# pwr_block.net
KiCad netlist of a schematic drawn in EAGLE
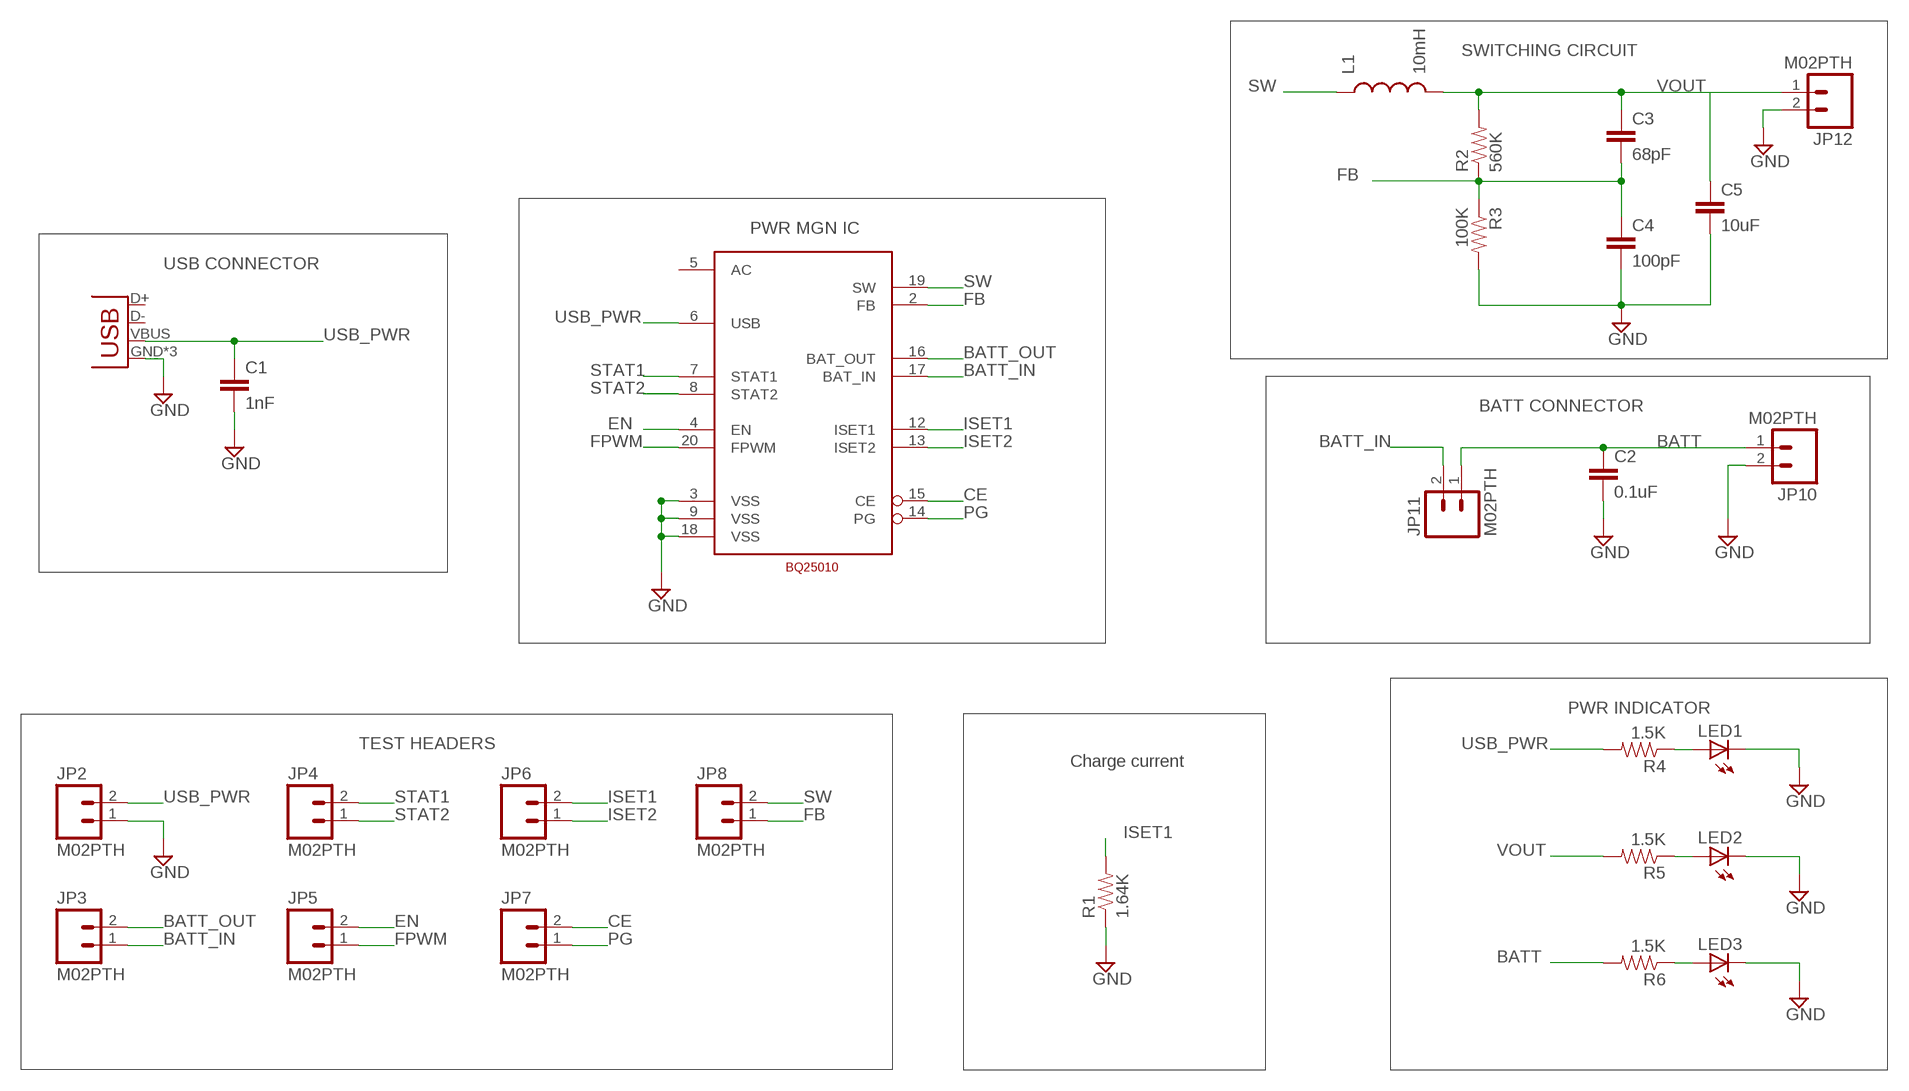
[diagram p0: schematic, sheet 1]

(export (version "E")
  (design (tool "Eeschema 10.0.6"))
  (components
    (comp (ref "C1")
      (value "1nF")
      (footprint "eagle-import:0603-CAP")
      (libsource (lib "eagle-import") (part "1NF/1000PF-50V-10%(0603)"))
    )
    (comp (ref "C2")
      (value "0.1uF")
      (footprint "eagle-import:0603-CAP")
      (libsource (lib "eagle-import") (part "0.1UF-100V-10%(0603)"))
    )
    (comp (ref "C3")
      (value "68pF")
      (footprint "eagle-import:0603-CAP")
      (libsource (lib "eagle-import") (part "10UF-6.3V-20%(0603)"))
    )
    (comp (ref "C4")
      (value "100pF")
      (footprint "eagle-import:0603-CAP")
      (libsource (lib "eagle-import") (part "10UF-6.3V-20%(0603)"))
    )
    (comp (ref "C5")
      (value "10uF")
      (footprint "eagle-import:0603-CAP")
      (libsource (lib "eagle-import") (part "10UF-6.3V-20%(0603)"))
    )
    (comp (ref "JP1")
      (value "USB-MICROB")
      (footprint "eagle-import:USB-MICROB")
      (description "CONN RCPT STD MICRO USB TYPE B")
      (libsource (lib "eagle-import") (part "USB-MICROB"))
    )
    (comp (ref "JP2")
      (value "M02PTH")
      (footprint "eagle-import:1X02")
      (libsource (lib "eagle-import") (part "M02PTH"))
    )
    (comp (ref "JP3")
      (value "M02PTH")
      (footprint "eagle-import:1X02")
      (libsource (lib "eagle-import") (part "M02PTH"))
    )
    (comp (ref "JP4")
      (value "M02PTH")
      (footprint "eagle-import:1X02")
      (libsource (lib "eagle-import") (part "M02PTH"))
    )
    (comp (ref "JP5")
      (value "M02PTH")
      (footprint "eagle-import:1X02")
      (libsource (lib "eagle-import") (part "M02PTH"))
    )
    (comp (ref "JP6")
      (value "M02PTH")
      (footprint "eagle-import:1X02")
      (libsource (lib "eagle-import") (part "M02PTH"))
    )
    (comp (ref "JP7")
      (value "M02PTH")
      (footprint "eagle-import:1X02")
      (libsource (lib "eagle-import") (part "M02PTH"))
    )
    (comp (ref "JP8")
      (value "M02PTH")
      (footprint "eagle-import:1X02")
      (libsource (lib "eagle-import") (part "M02PTH"))
    )
    (comp (ref "JP10")
      (value "M02PTH")
      (footprint "eagle-import:1X02")
      (libsource (lib "eagle-import") (part "M02PTH"))
    )
    (comp (ref "JP11")
      (value "M02PTH")
      (footprint "eagle-import:1X02")
      (libsource (lib "eagle-import") (part "M02PTH"))
    )
    (comp (ref "JP12")
      (value "M02PTH")
      (footprint "eagle-import:1X02")
      (libsource (lib "eagle-import") (part "M02PTH"))
    )
    (comp (ref "L1")
      (value "10mH")
      (footprint "eagle-import:0603")
      (libsource (lib "eagle-import") (part "INDUCTOR0603"))
    )
    (comp (ref "LED1")
      (value "LED0603")
      (footprint "eagle-import:LED-0603")
      (libsource (lib "eagle-import") (part "LED0603"))
    )
    (comp (ref "LED2")
      (value "LED0603")
      (footprint "eagle-import:LED-0603")
      (libsource (lib "eagle-import") (part "LED0603"))
    )
    (comp (ref "LED3")
      (value "LED0603")
      (footprint "eagle-import:LED-0603")
      (libsource (lib "eagle-import") (part "LED0603"))
    )
    (comp (ref "R1")
      (value "1.64K")
      (footprint "eagle-import:0603-RES")
      (libsource (lib "eagle-import") (part "RESISTOR0603-RES"))
    )
    (comp (ref "R2")
      (value "560K")
      (footprint "eagle-import:0603-RES")
      (libsource (lib "eagle-import") (part "RESISTOR0603-RES"))
    )
    (comp (ref "R3")
      (value "100K")
      (footprint "eagle-import:0603-RES")
      (libsource (lib "eagle-import") (part "RESISTOR0603-RES"))
    )
    (comp (ref "R4")
      (value "1.5K")
      (footprint "eagle-import:0603-RES")
      (libsource (lib "eagle-import") (part "RESISTOR0603-RES"))
    )
    (comp (ref "R5")
      (value "1.5K")
      (footprint "eagle-import:0603-RES")
      (libsource (lib "eagle-import") (part "RESISTOR0603-RES"))
    )
    (comp (ref "R6")
      (value "1.5K")
      (footprint "eagle-import:0603-RES")
      (libsource (lib "eagle-import") (part "RESISTOR0603-RES"))
    )
    (comp (ref "U$1")
      (value "BQ25010")
      (footprint "eagle-import:VQFN_RHL_20PIN")
      (libsource (lib "eagle-import") (part "BQ25010"))
    )
  )
  (nets
    (net (code "1") (name "/BATT") (class "Default")
      (node (ref "C2") (pin "1") (pinfunction "1_1") (pintype "passive"))
      (node (ref "JP10") (pin "1") (pinfunction "1_1") (pintype "passive"))
      (node (ref "JP11") (pin "1") (pinfunction "1_1") (pintype "passive"))
      (node (ref "R6") (pin "2") (pinfunction "2_2") (pintype "passive"))
    )
    (net (code "2") (name "/BATT_IN") (class "Default")
      (node (ref "JP11") (pin "2") (pinfunction "2_2") (pintype "passive"))
      (node (ref "JP3") (pin "1") (pinfunction "1_1") (pintype "passive"))
      (node (ref "U$1") (pin "17") (pinfunction "BAT_IN_17") (pintype "bidirectional"))
    )
    (net (code "3") (name "/BATT_OUT") (class "Default")
      (node (ref "JP3") (pin "2") (pinfunction "2_2") (pintype "passive"))
      (node (ref "U$1") (pin "16") (pinfunction "BAT_OUT_16") (pintype "bidirectional"))
    )
    (net (code "4") (name "/CE") (class "Default")
      (node (ref "JP7") (pin "2") (pinfunction "2_2") (pintype "passive"))
      (node (ref "U$1") (pin "15") (pinfunction "CE_15") (pintype "bidirectional"))
    )
    (net (code "5") (name "/EN") (class "Default")
      (node (ref "JP5") (pin "2") (pinfunction "2_2") (pintype "passive"))
      (node (ref "U$1") (pin "4") (pinfunction "EN_4") (pintype "bidirectional"))
    )
    (net (code "6") (name "/FB") (class "Default")
      (node (ref "C3") (pin "2") (pinfunction "2_2") (pintype "passive"))
      (node (ref "C4") (pin "1") (pinfunction "1_1") (pintype "passive"))
      (node (ref "JP8") (pin "1") (pinfunction "1_1") (pintype "passive"))
      (node (ref "R2") (pin "1") (pinfunction "1_1") (pintype "passive"))
      (node (ref "R3") (pin "1") (pinfunction "1_1") (pintype "passive"))
      (node (ref "U$1") (pin "2") (pinfunction "FB_2") (pintype "bidirectional"))
    )
    (net (code "7") (name "/FPWM") (class "Default")
      (node (ref "JP5") (pin "1") (pinfunction "1_1") (pintype "passive"))
      (node (ref "U$1") (pin "20") (pinfunction "FPWM_20") (pintype "bidirectional"))
    )
    (net (code "8") (name "/ISET1") (class "Default")
      (node (ref "JP6") (pin "2") (pinfunction "2_2") (pintype "passive"))
      (node (ref "R1") (pin "2") (pinfunction "2_2") (pintype "passive"))
      (node (ref "U$1") (pin "12") (pinfunction "ISET1_12") (pintype "bidirectional"))
    )
    (net (code "9") (name "/ISET2") (class "Default")
      (node (ref "JP6") (pin "1") (pinfunction "1_1") (pintype "passive"))
      (node (ref "U$1") (pin "13") (pinfunction "ISET2_13") (pintype "bidirectional"))
    )
    (net (code "10") (name "/PG") (class "Default")
      (node (ref "JP7") (pin "1") (pinfunction "1_1") (pintype "passive"))
      (node (ref "U$1") (pin "14") (pinfunction "PG_14") (pintype "bidirectional"))
    )
    (net (code "11") (name "/STAT1") (class "Default")
      (node (ref "JP4") (pin "2") (pinfunction "2_2") (pintype "passive"))
      (node (ref "U$1") (pin "7") (pinfunction "STAT1_7") (pintype "bidirectional"))
    )
    (net (code "12") (name "/STAT2") (class "Default")
      (node (ref "JP4") (pin "1") (pinfunction "1_1") (pintype "passive"))
      (node (ref "U$1") (pin "8") (pinfunction "STAT2_8") (pintype "bidirectional"))
    )
    (net (code "13") (name "/SW") (class "Default")
      (node (ref "JP8") (pin "2") (pinfunction "2_2") (pintype "passive"))
      (node (ref "L1") (pin "1") (pinfunction "1_1") (pintype "passive"))
      (node (ref "U$1") (pin "19") (pinfunction "SW_19") (pintype "bidirectional"))
    )
    (net (code "14") (name "/USB_PWR") (class "Default")
      (node (ref "C1") (pin "1") (pinfunction "1_1") (pintype "passive"))
      (node (ref "JP1") (pin "VBUS") (pinfunction "VBUS_VBUS") (pintype "bidirectional"))
      (node (ref "JP2") (pin "2") (pinfunction "2_2") (pintype "passive"))
      (node (ref "R4") (pin "2") (pinfunction "2_2") (pintype "passive"))
      (node (ref "U$1") (pin "6") (pinfunction "USB_6") (pintype "bidirectional"))
    )
    (net (code "15") (name "/VOUT") (class "Default")
      (node (ref "C3") (pin "1") (pinfunction "1_1") (pintype "passive"))
      (node (ref "C5") (pin "1") (pinfunction "1_1") (pintype "passive"))
      (node (ref "JP12") (pin "1") (pinfunction "1_1") (pintype "passive"))
      (node (ref "L1") (pin "2") (pinfunction "2_2") (pintype "passive"))
      (node (ref "R2") (pin "2") (pinfunction "2_2") (pintype "passive"))
      (node (ref "R5") (pin "2") (pinfunction "2_2") (pintype "passive"))
    )
    (net (code "16") (name "GND") (class "Default")
      (node (ref "C1") (pin "2") (pinfunction "2_2") (pintype "passive"))
      (node (ref "C2") (pin "2") (pinfunction "2_2") (pintype "passive"))
      (node (ref "C4") (pin "2") (pinfunction "2_2") (pintype "passive"))
      (node (ref "C5") (pin "2") (pinfunction "2_2") (pintype "passive"))
      (node (ref "JP1") (pin "GND") (pinfunction "GND_GND") (pintype "bidirectional"))
      (node (ref "JP1") (pin "MT1") (pinfunction "GND_MT1") (pintype "bidirectional"))
      (node (ref "JP1") (pin "MT2") (pinfunction "GND_MT2") (pintype "bidirectional"))
      (node (ref "JP10") (pin "2") (pinfunction "2_2") (pintype "passive"))
      (node (ref "JP12") (pin "2") (pinfunction "2_2") (pintype "passive"))
      (node (ref "JP2") (pin "1") (pinfunction "1_1") (pintype "passive"))
      (node (ref "LED1") (pin "C") (pinfunction "C_C") (pintype "passive"))
      (node (ref "LED2") (pin "C") (pinfunction "C_C") (pintype "passive"))
      (node (ref "LED3") (pin "C") (pinfunction "C_C") (pintype "passive"))
      (node (ref "R1") (pin "1") (pinfunction "1_1") (pintype "passive"))
      (node (ref "R3") (pin "2") (pinfunction "2_2") (pintype "passive"))
      (node (ref "U$1") (pin "18") (pinfunction "VSS_18") (pintype "bidirectional"))
      (node (ref "U$1") (pin "3") (pinfunction "VSS_3") (pintype "bidirectional"))
      (node (ref "U$1") (pin "9") (pinfunction "VSS_9") (pintype "bidirectional"))
    )
    (net (code "17") (name "Net-(LED1-PadA)") (class "Default")
      (node (ref "LED1") (pin "A") (pinfunction "A_A") (pintype "passive"))
      (node (ref "R4") (pin "1") (pinfunction "1_1") (pintype "passive"))
    )
    (net (code "18") (name "Net-(LED2-PadA)") (class "Default")
      (node (ref "LED2") (pin "A") (pinfunction "A_A") (pintype "passive"))
      (node (ref "R5") (pin "1") (pinfunction "1_1") (pintype "passive"))
    )
    (net (code "19") (name "Net-(LED3-PadA)") (class "Default")
      (node (ref "LED3") (pin "A") (pinfunction "A_A") (pintype "passive"))
      (node (ref "R6") (pin "1") (pinfunction "1_1") (pintype "passive"))
    )
    (net (code "20") (name "unconnected-(JP1-PadD+)") (class "Default")
      (node (ref "JP1") (pin "D+") (pinfunction "D+_D+") (pintype "bidirectional"))
    )
    (net (code "21") (name "unconnected-(JP1-PadD-)") (class "Default")
      (node (ref "JP1") (pin "D-") (pinfunction "D-_D-") (pintype "bidirectional"))
    )
    (net (code "22") (name "unconnected-(U$1-AC-Pad5)") (class "Default")
      (node (ref "U$1") (pin "5") (pinfunction "AC_5") (pintype "bidirectional"))
    )
  )
)
